# CON_SPDIF_INOUT.net
KiCad netlist of a schematic drawn in Altium Designer
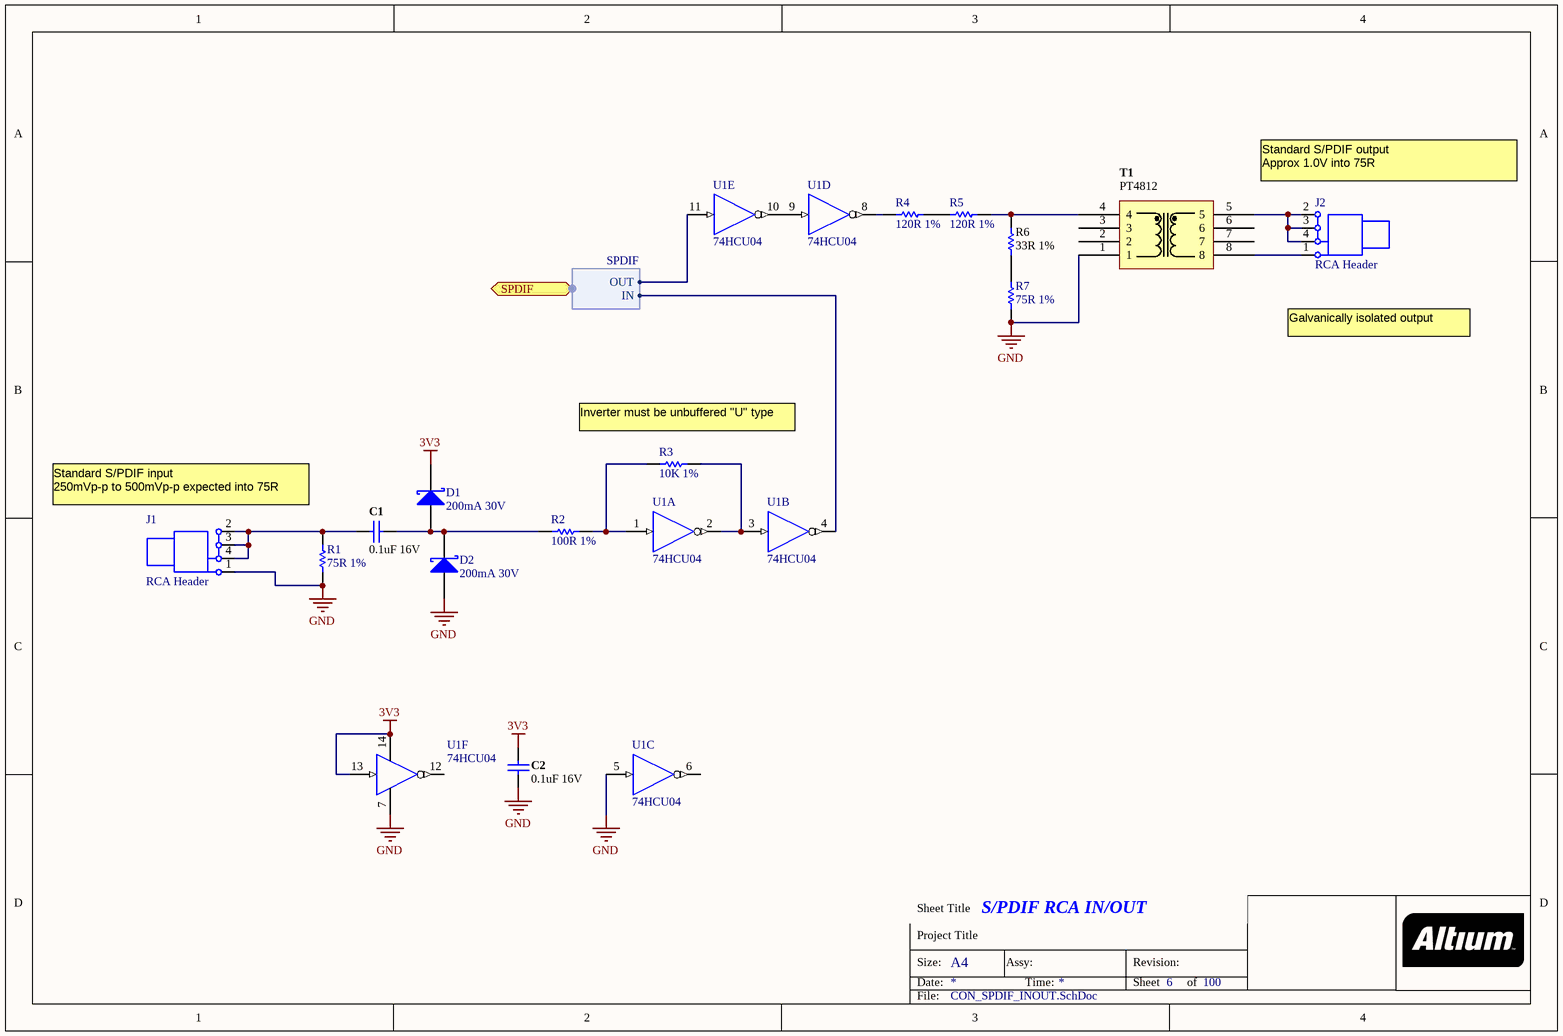
[diagram p0: CON_SPDIF_INOUT.SchDoc]

(export (version "E")
  (design (tool "Eeschema 10.0.6"))
  (components
    (comp (ref "C1")
      (value "0.1uF 16V")
      (footprint "CAPC1005-STAR")
      (description "Capacitor, Ceramic, 0.1uF 10% 16V 0402 (1005) X7R")
      (fields (field (name "TOLERANCE") "10 %"))
      (libsource (lib "AltiumDesignLibrary") (part "CAP-NP"))
    )
    (comp (ref "C2")
      (value "0.1uF 16V")
      (footprint "CAPC1005-STAR")
      (description "Capacitor, Ceramic, 0.1uF 10% 16V 0402 (1005) X7R")
      (fields (field (name "TOLERANCE") "10 %"))
      (libsource (lib "") (part "CAP-NP_1"))
    )
    (comp (ref "D1")
      (value "200mA 30V")
      (footprint "SOT95P230-3C")
      (description "Schottky Diode, BAT54 30V 200mA 30V SOT-23")
      (libsource (lib "AltiumDesignLibrary") (part "DIO-SCHOTTKY-1S-SOT23"))
    )
    (comp (ref "D2")
      (value "200mA 30V")
      (footprint "SOT95P230-3C")
      (description "Schottky Diode, BAT54 30V 200mA 30V SOT-23")
      (libsource (lib "AltiumDesignLibrary") (part "DIO-SCHOTTKY-1S-SOT23"))
    )
    (comp (ref "J1")
      (value "RCA Header")
      (footprint "TRC-005")
      (description "Connector, TRC-005-4 , RCA Phono Jack, Right Angle, Thru-Hole, Snap-In")
      (libsource (lib "AltiumDesignLibrary") (part "CON-RCA-RA"))
    )
    (comp (ref "J2")
      (value "RCA Header")
      (footprint "TRC-005")
      (description "Connector, TRC-005-4 , RCA Phono Jack, Right Angle, Thru-Hole, Snap-In")
      (libsource (lib "AltiumDesignLibrary") (part "CON-RCA-RA"))
    )
    (comp (ref "R1")
      (value "75R 1%")
      (footprint "RESC1005-STAR")
      (description "Resistor, 75R 1% 0402")
      (fields (field (name "TOLERANCE") "1 %"))
      (libsource (lib "AltiumDesignLibrary") (part "RES"))
    )
    (comp (ref "R2")
      (value "100R 1%")
      (footprint "RESC1005-STAR")
      (description "Resistor, 100R 1% 0402 (1005)")
      (fields (field (name "TOLERANCE") "1 %"))
      (libsource (lib "AltiumDesignLibrary") (part "RES"))
    )
    (comp (ref "R3")
      (value "10K 1%")
      (footprint "RESC1005-STAR")
      (description "Resistor, 10K 1% 0402 (1005)")
      (fields (field (name "TOLERANCE") "1 %"))
      (libsource (lib "AltiumDesignLibrary") (part "RES"))
    )
    (comp (ref "R4")
      (value "120R 1%")
      (footprint "RESC1005-STAR")
      (description "Resistor, 120R 1% 0402 (1005)")
      (fields (field (name "TOLERANCE") "1 %"))
      (libsource (lib "AltiumDesignLibrary") (part "RES"))
    )
    (comp (ref "R5")
      (value "120R 1%")
      (footprint "RESC1005-STAR")
      (description "Resistor, 120R 1% 0402 (1005)")
      (fields (field (name "TOLERANCE") "1 %"))
      (libsource (lib "AltiumDesignLibrary") (part "RES"))
    )
    (comp (ref "R6")
      (value "33R 1%")
      (footprint "RESC1005-STAR")
      (description "Resistor, 33R 1% 0402 (1005)")
      (fields (field (name "TOLERANCE") "1 %"))
      (libsource (lib "AltiumDesignLibrary") (part "RES"))
    )
    (comp (ref "R7")
      (value "75R 1%")
      (footprint "RESC1005-STAR")
      (description "Resistor, 75R 1% 0402")
      (fields (field (name "TOLERANCE") "1 %"))
      (libsource (lib "AltiumDesignLibrary") (part "RES"))
    )
    (comp (ref "T1")
      (value "PT4812")
      (footprint "PT4812")
      (description "Transformer, 1:1, SMD, 0 to 70 deg C,  1 to 7 Mbps, 500Vrms min")
      (libsource (lib "AltiumDesignLibrary") (part "PT4812"))
    )
    (comp (ref "U1")
      (value "74HCU04")
      (footprint "SOIC127P600-14")
      (description "74HCU04, HEX Inverter, Unbuffered")
      (libsource (lib "AltiumDesignLibrary") (part "74xx04"))
    )
  )
  (nets
    (net (code "2") (name "/IN") (class "Default")
      (node (ref "U1") (pin "4") (pinfunction "Y_4") (pintype "output"))
    )
    (net (code "3") (name "/OUT") (class "Default")
      (node (ref "U1") (pin "11") (pinfunction "A_11") (pintype "input"))
    )
    (net (code "5") (name "3V3") (class "Default")
      (node (ref "C2") (pin "2") (pinfunction "2_2") (pintype "passive"))
      (node (ref "D1") (pin "3") (pinfunction "k_3") (pintype "passive"))
      (node (ref "U1") (pin "13") (pinfunction "A_13") (pintype "input"))
      (node (ref "U1") (pin "14") (pinfunction "VCC_14") (pintype "power_in"))
    )
    (net (code "6") (name "GND") (class "Default")
      (node (ref "C2") (pin "1") (pinfunction "1_1") (pintype "passive"))
      (node (ref "D2") (pin "1") (pinfunction "A_1") (pintype "passive"))
      (node (ref "J1") (pin "1") (pinfunction "Black_1") (pintype "passive"))
      (node (ref "R1") (pin "2") (pinfunction "2_2") (pintype "passive"))
      (node (ref "R7") (pin "2") (pinfunction "2_2") (pintype "passive"))
      (node (ref "T1") (pin "1") (pinfunction "1_1") (pintype "passive"))
      (node (ref "U1") (pin "5") (pinfunction "A_5") (pintype "input"))
      (node (ref "U1") (pin "7") (pinfunction "GND_7") (pintype "power_in"))
    )
    (net (code "7") (name "Net-(D1-A)") (class "Default")
      (node (ref "C1") (pin "2") (pinfunction "2_2") (pintype "passive"))
      (node (ref "D1") (pin "1") (pinfunction "A_1") (pintype "passive"))
      (node (ref "D2") (pin "3") (pinfunction "k_3") (pintype "passive"))
      (node (ref "R2") (pin "2") (pinfunction "2_2") (pintype "passive"))
    )
    (net (code "8") (name "Net-(J1-Red)") (class "Default")
      (node (ref "C1") (pin "1") (pinfunction "1_1") (pintype "passive"))
      (node (ref "J1") (pin "2") (pinfunction "Yellow_2") (pintype "passive"))
      (node (ref "J1") (pin "3") (pinfunction "White_3") (pintype "passive"))
      (node (ref "J1") (pin "4") (pinfunction "Red_4") (pintype "passive"))
      (node (ref "R1") (pin "1") (pinfunction "1_1") (pintype "passive"))
    )
    (net (code "9") (name "Net-(J2-Black)") (class "Default")
      (node (ref "J2") (pin "1") (pinfunction "Black_1") (pintype "passive"))
      (node (ref "T1") (pin "8") (pinfunction "8_8") (pintype "passive"))
    )
    (net (code "10") (name "Net-(J2-Red)") (class "Default")
      (node (ref "J2") (pin "2") (pinfunction "Yellow_2") (pintype "passive"))
      (node (ref "J2") (pin "3") (pinfunction "White_3") (pintype "passive"))
      (node (ref "J2") (pin "4") (pinfunction "Red_4") (pintype "passive"))
      (node (ref "T1") (pin "5") (pinfunction "5_5") (pintype "passive"))
    )
    (net (code "11") (name "Net-(R4-Pad2)") (class "Default")
      (node (ref "R4") (pin "2") (pinfunction "2_2") (pintype "passive"))
      (node (ref "R5") (pin "1") (pinfunction "1_1") (pintype "passive"))
    )
    (net (code "12") (name "Net-(R5-Pad2)") (class "Default")
      (node (ref "R5") (pin "2") (pinfunction "2_2") (pintype "passive"))
      (node (ref "R6") (pin "2") (pinfunction "2_2") (pintype "passive"))
      (node (ref "T1") (pin "4") (pinfunction "4_4") (pintype "passive"))
    )
    (net (code "13") (name "Net-(R6-Pad1)") (class "Default")
      (node (ref "R6") (pin "1") (pinfunction "1_1") (pintype "passive"))
      (node (ref "R7") (pin "1") (pinfunction "1_1") (pintype "passive"))
    )
    (net (code "14") (name "Net-(U1A-A)") (class "Default")
      (node (ref "R2") (pin "1") (pinfunction "1_1") (pintype "passive"))
      (node (ref "R3") (pin "1") (pinfunction "1_1") (pintype "passive"))
      (node (ref "U1") (pin "1") (pinfunction "A_1") (pintype "input"))
    )
    (net (code "15") (name "Net-(U1A-Y)") (class "Default")
      (node (ref "R3") (pin "2") (pinfunction "2_2") (pintype "passive"))
      (node (ref "U1") (pin "2") (pinfunction "Y_2") (pintype "output"))
      (node (ref "U1") (pin "3") (pinfunction "A_3") (pintype "input"))
    )
    (net (code "16") (name "Net-(U1D-A)") (class "Default")
      (node (ref "U1") (pin "10") (pinfunction "Y_10") (pintype "output"))
      (node (ref "U1") (pin "9") (pinfunction "A_9") (pintype "input"))
    )
    (net (code "17") (name "Net-(U1D-Y)") (class "Default")
      (node (ref "R4") (pin "1") (pinfunction "1_1") (pintype "passive"))
      (node (ref "U1") (pin "8") (pinfunction "Y_8") (pintype "output"))
    )
    (net (code "18") (name "unconnected-(D1-Pad2)") (class "Default")
      (node (ref "D1") (pin "2") (pintype "passive"))
    )
    (net (code "19") (name "unconnected-(D2-Pad2)") (class "Default")
      (node (ref "D2") (pin "2") (pintype "passive"))
    )
    (net (code "20") (name "unconnected-(T1-Pad2)") (class "Default")
      (node (ref "T1") (pin "2") (pinfunction "2_2") (pintype "passive"))
    )
    (net (code "21") (name "unconnected-(T1-Pad3)") (class "Default")
      (node (ref "T1") (pin "3") (pinfunction "3_3") (pintype "passive"))
    )
    (net (code "22") (name "unconnected-(T1-Pad6)") (class "Default")
      (node (ref "T1") (pin "6") (pinfunction "6_6") (pintype "passive"))
    )
    (net (code "23") (name "unconnected-(T1-Pad7)") (class "Default")
      (node (ref "T1") (pin "7") (pinfunction "7_7") (pintype "passive"))
    )
    (net (code "24") (name "unconnected-(U1C-Y-Pad6)") (class "Default")
      (node (ref "U1") (pin "6") (pinfunction "Y_6") (pintype "output"))
    )
    (net (code "25") (name "unconnected-(U1F-Y-Pad12)") (class "Default")
      (node (ref "U1") (pin "12") (pinfunction "Y_12") (pintype "output"))
    )
  )
)
